# SCD30_pcb.net
KiCad netlist of a schematic drawn in EAGLE
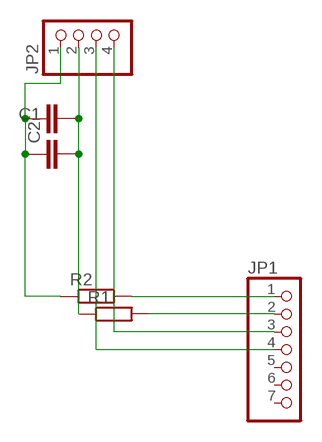
[diagram p0: schematic, sheet 1]

(export (version "E")
  (design (tool "Eeschema 10.0.6"))
  (components
    (comp (ref "C1")
      (value "C2,5-3")
      (footprint "eagle-import:C2.5-3")
      (libsource (lib "eagle-import") (part "C2,5-3"))
    )
    (comp (ref "C2")
      (value "C5/2.5")
      (footprint "eagle-import:C5B2.5")
      (libsource (lib "eagle-import") (part "C5/2.5"))
    )
    (comp (ref "JP1")
      (value "PINHD-1X7")
      (footprint "eagle-import:1X07")
      (libsource (lib "eagle-import") (part "PINHD-1X7"))
    )
    (comp (ref "JP2")
      (value "PINHD-1X4/90")
      (footprint "eagle-import:1X04_90")
      (libsource (lib "eagle-import") (part "PINHD-1X4/90"))
    )
    (comp (ref "R1")
      (value "R-EU_0204/7")
      (footprint "eagle-import:0204_7")
      (libsource (lib "eagle-import") (part "R-EU_0204/7"))
    )
    (comp (ref "R2")
      (value "R-EU_0204/7")
      (footprint "eagle-import:0204_7")
      (libsource (lib "eagle-import") (part "R-EU_0204/7"))
    )
  )
  (nets
    (net (code "1") (name "Net-(C1-Pad1)") (class "Default")
      (node (ref "C1") (pin "1") (pinfunction "1_1") (pintype "passive"))
      (node (ref "C2") (pin "1") (pinfunction "1_1") (pintype "passive"))
      (node (ref "JP2") (pin "1") (pinfunction "1_1") (pintype "passive"))
      (node (ref "R2") (pin "1") (pinfunction "1_1") (pintype "passive"))
    )
    (net (code "2") (name "Net-(C1-Pad2)") (class "Default")
      (node (ref "C1") (pin "2") (pinfunction "2_2") (pintype "passive"))
      (node (ref "C2") (pin "2") (pinfunction "2_2") (pintype "passive"))
      (node (ref "JP2") (pin "2") (pinfunction "2_2") (pintype "passive"))
      (node (ref "R1") (pin "1") (pinfunction "1_1") (pintype "passive"))
    )
    (net (code "3") (name "Net-(JP1-Pad1)") (class "Default")
      (node (ref "JP1") (pin "1") (pinfunction "1_1") (pintype "passive"))
      (node (ref "R2") (pin "2") (pinfunction "2_2") (pintype "passive"))
    )
    (net (code "4") (name "Net-(JP1-Pad2)") (class "Default")
      (node (ref "JP1") (pin "2") (pinfunction "2_2") (pintype "passive"))
      (node (ref "R1") (pin "2") (pinfunction "2_2") (pintype "passive"))
    )
    (net (code "5") (name "Net-(JP1-Pad3)") (class "Default")
      (node (ref "JP1") (pin "3") (pinfunction "3_3") (pintype "passive"))
      (node (ref "JP2") (pin "4") (pinfunction "4_4") (pintype "passive"))
    )
    (net (code "6") (name "Net-(JP1-Pad4)") (class "Default")
      (node (ref "JP1") (pin "4") (pinfunction "4_4") (pintype "passive"))
      (node (ref "JP2") (pin "3") (pinfunction "3_3") (pintype "passive"))
    )
    (net (code "7") (name "unconnected-(JP1-Pad5)") (class "Default")
      (node (ref "JP1") (pin "5") (pinfunction "5_5") (pintype "passive"))
    )
    (net (code "8") (name "unconnected-(JP1-Pad6)") (class "Default")
      (node (ref "JP1") (pin "6") (pinfunction "6_6") (pintype "passive"))
    )
    (net (code "9") (name "unconnected-(JP1-Pad7)") (class "Default")
      (node (ref "JP1") (pin "7") (pinfunction "7_7") (pintype "passive"))
    )
  )
)
